# Output.net
KiCad netlist of a schematic drawn in Altium Designer
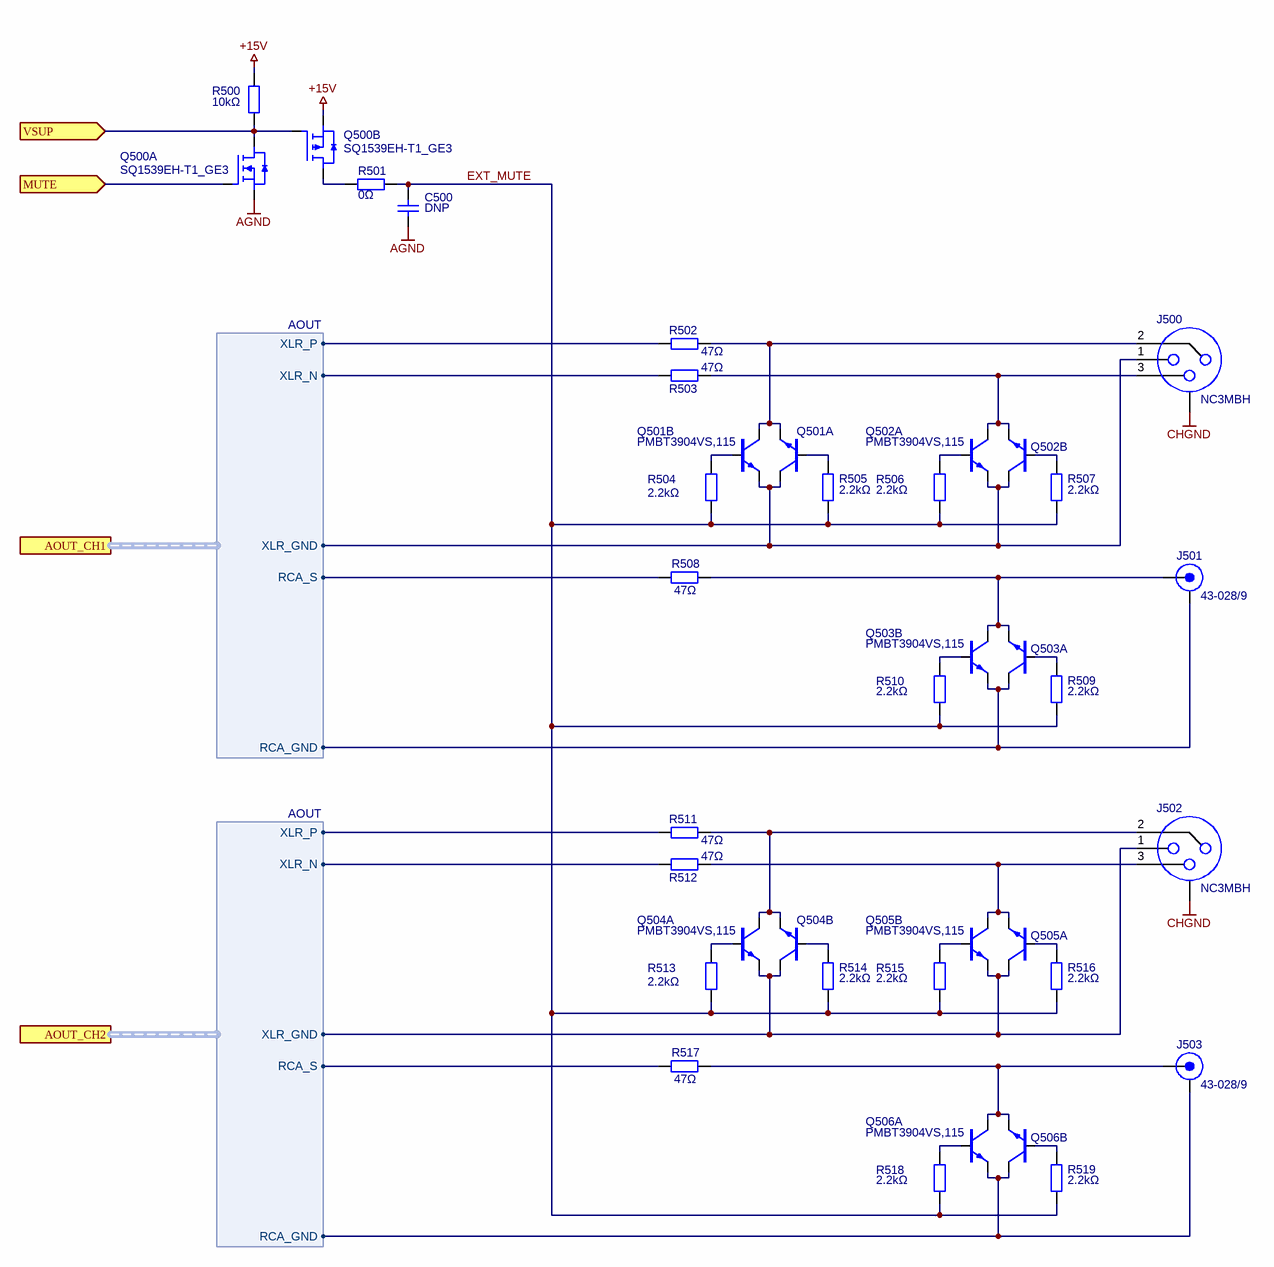
[diagram p0: Output.SchDoc]

(export (version "E")
  (design (tool "Eeschema 10.0.6"))
  (components
    (comp (ref "C500")
      (value "DNP")
      (footprint "SMD0603CAP")
      (description "Ceramic Capacitor")
      (libsource (lib "Audio-Streamer") (part "Capacitor Ceramic"))
    )
    (comp (ref "J500")
      (value "NC3MBH")
      (footprint "NC3MBH")
      (description "XLR Connector Male, Panel Mount")
      (libsource (lib "Audio-Streamer") (part "Connector XLR"))
    )
    (comp (ref "J501")
      (value "43-028/9")
      (footprint "RCA-Plug")
      (description "RCA Connector")
      (libsource (lib "Audio-Streamer") (part "Connector RCA"))
    )
    (comp (ref "J502")
      (value "NC3MBH")
      (footprint "NC3MBH")
      (description "XLR Connector Male, Panel Mount")
      (libsource (lib "Audio-Streamer") (part "Connector XLR"))
    )
    (comp (ref "J503")
      (value "43-028/9")
      (footprint "RCA-Plug")
      (description "RCA Connector")
      (libsource (lib "Audio-Streamer") (part "Connector RCA"))
    )
    (comp (ref "Q500")
      (value "SQ1539EH-T1_GE3")
      (footprint "SOT-363-6")
      (description "Transistor Dual, NMOS & PMOS")
      (libsource (lib "Audio-Streamer") (part "Transistor N/PMOS Dual"))
    )
    (comp (ref "Q501")
      (value "PMBT3904VS,115")
      (footprint "SOT-666")
      (description "Transistor Bipolar Dual")
      (libsource (lib "Audio-Streamer") (part "Transistor Bipolar Dual"))
    )
    (comp (ref "Q502")
      (value "PMBT3904VS,115")
      (footprint "SOT-666")
      (description "Transistor Bipolar Dual")
      (libsource (lib "Audio-Streamer") (part "Transistor Bipolar Dual"))
    )
    (comp (ref "Q503")
      (value "PMBT3904VS,115")
      (footprint "SOT-666")
      (description "Transistor Bipolar Dual")
      (libsource (lib "Audio-Streamer") (part "Transistor Bipolar Dual"))
    )
    (comp (ref "Q504")
      (value "PMBT3904VS,115")
      (footprint "SOT-666")
      (description "Transistor Bipolar Dual")
      (libsource (lib "Audio-Streamer") (part "Transistor Bipolar Dual"))
    )
    (comp (ref "Q505")
      (value "PMBT3904VS,115")
      (footprint "SOT-666")
      (description "Transistor Bipolar Dual")
      (libsource (lib "") (part "Transistor Bipolar Dual_1"))
    )
    (comp (ref "Q506")
      (value "PMBT3904VS,115")
      (footprint "SOT-666")
      (description "Transistor Bipolar Dual")
      (libsource (lib "Audio-Streamer") (part "Transistor Bipolar Dual"))
    )
    (comp (ref "R500")
      (value "10kΩ")
      (footprint "SMD0603RES")
      (description "Resistor")
      (libsource (lib "") (part "Resistor_1"))
    )
    (comp (ref "R501")
      (value "0Ω")
      (footprint "SMD0603RES")
      (description "Resistor")
      (libsource (lib "Audio-Streamer") (part "Resistor"))
    )
    (comp (ref "R502")
      (value "47Ω")
      (footprint "SMD0603RES")
      (description "Resistor Thin Film")
      (fields (field (name "MANUFACTURER PART NO.") "TNPW060347R0BEEA"))
      (libsource (lib "Audio-Streamer") (part "Resistor"))
    )
    (comp (ref "R503")
      (value "47Ω")
      (footprint "SMD0603RES")
      (description "Resistor Thin Film")
      (fields (field (name "MANUFACTURER PART NO.") "TNPW060347R0BEEA"))
      (libsource (lib "Audio-Streamer") (part "Resistor"))
    )
    (comp (ref "R504")
      (value "2.2kΩ")
      (footprint "SMD0603RES")
      (description "Resistor")
      (libsource (lib "") (part "Resistor_1"))
    )
    (comp (ref "R505")
      (value "2.2kΩ")
      (footprint "SMD0603RES")
      (description "Resistor")
      (libsource (lib "") (part "Resistor_2"))
    )
    (comp (ref "R506")
      (value "2.2kΩ")
      (footprint "SMD0603RES")
      (description "Resistor")
      (libsource (lib "") (part "Resistor_1"))
    )
    (comp (ref "R507")
      (value "2.2kΩ")
      (footprint "SMD0603RES")
      (description "Resistor")
      (libsource (lib "") (part "Resistor_2"))
    )
    (comp (ref "R508")
      (value "47Ω")
      (footprint "SMD0603RES")
      (description "Resistor Thin Film")
      (fields (field (name "MANUFACTURER PART NO.") "TNPW060347R0BEEA"))
      (libsource (lib "Audio-Streamer") (part "Resistor"))
    )
    (comp (ref "R509")
      (value "2.2kΩ")
      (footprint "SMD0603RES")
      (description "Resistor")
      (libsource (lib "") (part "Resistor_2"))
    )
    (comp (ref "R510")
      (value "2.2kΩ")
      (footprint "SMD0603RES")
      (description "Resistor")
      (libsource (lib "") (part "Resistor_1"))
    )
    (comp (ref "R511")
      (value "47Ω")
      (footprint "SMD0603RES")
      (description "Resistor Thin Film")
      (fields (field (name "MANUFACTURER PART NO.") "TNPW060347R0BEEA"))
      (libsource (lib "Audio-Streamer") (part "Resistor"))
    )
    (comp (ref "R512")
      (value "47Ω")
      (footprint "SMD0603RES")
      (description "Resistor Thin Film")
      (fields (field (name "MANUFACTURER PART NO.") "TNPW060347R0BEEA"))
      (libsource (lib "Audio-Streamer") (part "Resistor"))
    )
    (comp (ref "R513")
      (value "2.2kΩ")
      (footprint "SMD0603RES")
      (description "Resistor")
      (libsource (lib "") (part "Resistor_1"))
    )
    (comp (ref "R514")
      (value "2.2kΩ")
      (footprint "SMD0603RES")
      (description "Resistor")
      (libsource (lib "") (part "Resistor_2"))
    )
    (comp (ref "R515")
      (value "2.2kΩ")
      (footprint "SMD0603RES")
      (description "Resistor")
      (libsource (lib "") (part "Resistor_1"))
    )
    (comp (ref "R516")
      (value "2.2kΩ")
      (footprint "SMD0603RES")
      (description "Resistor")
      (libsource (lib "") (part "Resistor_2"))
    )
    (comp (ref "R517")
      (value "47Ω")
      (footprint "SMD0603RES")
      (description "Resistor Thin Film")
      (fields (field (name "MANUFACTURER PART NO.") "TNPW060347R0BEEA"))
      (libsource (lib "Audio-Streamer") (part "Resistor"))
    )
    (comp (ref "R518")
      (value "2.2kΩ")
      (footprint "SMD0603RES")
      (description "Resistor")
      (libsource (lib "") (part "Resistor_1"))
    )
    (comp (ref "R519")
      (value "2.2kΩ")
      (footprint "SMD0603RES")
      (description "Resistor")
      (libsource (lib "") (part "Resistor_2"))
    )
  )
  (nets
    (net (code "2") (name "+15V") (class "Default")
      (node (ref "Q500") (pin "4") (pinfunction "S_4") (pintype "passive"))
      (node (ref "R500") (pin "2") (pinfunction "2_2") (pintype "passive"))
    )
    (net (code "3") (name "/EXT_MUTE") (class "Default")
      (node (ref "C500") (pin "1") (pinfunction "1_1") (pintype "passive"))
      (node (ref "R501") (pin "1") (pinfunction "1_1") (pintype "passive"))
      (node (ref "R504") (pin "1") (pinfunction "1_1") (pintype "passive"))
      (node (ref "R505") (pin "1") (pinfunction "1_1") (pintype "passive"))
      (node (ref "R506") (pin "1") (pinfunction "1_1") (pintype "passive"))
      (node (ref "R507") (pin "1") (pinfunction "1_1") (pintype "passive"))
      (node (ref "R509") (pin "1") (pinfunction "1_1") (pintype "passive"))
      (node (ref "R510") (pin "1") (pinfunction "1_1") (pintype "passive"))
      (node (ref "R513") (pin "1") (pinfunction "1_1") (pintype "passive"))
      (node (ref "R514") (pin "1") (pinfunction "1_1") (pintype "passive"))
      (node (ref "R515") (pin "1") (pinfunction "1_1") (pintype "passive"))
      (node (ref "R516") (pin "1") (pinfunction "1_1") (pintype "passive"))
      (node (ref "R518") (pin "1") (pinfunction "1_1") (pintype "passive"))
      (node (ref "R519") (pin "1") (pinfunction "1_1") (pintype "passive"))
    )
    (net (code "4") (name "/MUTE") (class "Default")
      (node (ref "Q500") (pin "2") (pinfunction "G_2") (pintype "passive"))
    )
    (net (code "5") (name "/VSUP") (class "Default")
      (node (ref "Q500") (pin "5") (pinfunction "G_5") (pintype "passive"))
      (node (ref "Q500") (pin "6") (pinfunction "D_6") (pintype "passive"))
      (node (ref "R500") (pin "1") (pinfunction "1_1") (pintype "passive"))
    )
    (net (code "7") (name "AGND") (class "Default")
      (node (ref "C500") (pin "2") (pinfunction "q_2") (pintype "passive"))
      (node (ref "Q500") (pin "1") (pinfunction "S_1") (pintype "passive"))
    )
    (net (code "8") (name "CHGND") (class "Default")
      (node (ref "J500") (pin "0") (pinfunction "0_0") (pintype "passive"))
      (node (ref "J502") (pin "0") (pinfunction "0_0") (pintype "passive"))
    )
    (net (code "9") (name "Net-(J500-Pad1)") (class "Default")
      (node (ref "J500") (pin "1") (pinfunction "1_1") (pintype "passive"))
      (node (ref "Q501") (pin "4") (pinfunction "4_4") (pintype "passive"))
      (node (ref "Q501") (pin "6") (pinfunction "6_6") (pintype "passive"))
      (node (ref "Q502") (pin "1") (pinfunction "1_1") (pintype "passive"))
      (node (ref "Q502") (pin "3") (pinfunction "3_3") (pintype "passive"))
    )
    (net (code "10") (name "Net-(J500-Pad2)") (class "Default")
      (node (ref "J500") (pin "2") (pinfunction "2_2") (pintype "passive"))
      (node (ref "Q501") (pin "1") (pinfunction "1_1") (pintype "passive"))
      (node (ref "Q501") (pin "3") (pinfunction "3_3") (pintype "passive"))
      (node (ref "R502") (pin "1") (pinfunction "1_1") (pintype "passive"))
    )
    (net (code "11") (name "Net-(J500-Pad3)") (class "Default")
      (node (ref "J500") (pin "3") (pinfunction "3_3") (pintype "passive"))
      (node (ref "Q502") (pin "4") (pinfunction "4_4") (pintype "passive"))
      (node (ref "Q502") (pin "6") (pinfunction "6_6") (pintype "passive"))
      (node (ref "R503") (pin "1") (pinfunction "1_1") (pintype "passive"))
    )
    (net (code "12") (name "Net-(J501-Pad1)") (class "Default")
      (node (ref "J501") (pin "1") (pinfunction "1_1") (pintype "passive"))
      (node (ref "Q503") (pin "1") (pinfunction "1_1") (pintype "passive"))
      (node (ref "Q503") (pin "3") (pinfunction "3_3") (pintype "passive"))
      (node (ref "R508") (pin "1") (pinfunction "1_1") (pintype "passive"))
    )
    (net (code "13") (name "Net-(J501-Pad2)") (class "Default")
      (node (ref "J501") (pin "2") (pinfunction "2_2") (pintype "passive"))
      (node (ref "Q503") (pin "4") (pinfunction "4_4") (pintype "passive"))
      (node (ref "Q503") (pin "6") (pinfunction "6_6") (pintype "passive"))
    )
    (net (code "14") (name "Net-(J502-Pad1)") (class "Default")
      (node (ref "J502") (pin "1") (pinfunction "1_1") (pintype "passive"))
      (node (ref "Q504") (pin "1") (pinfunction "1_1") (pintype "passive"))
      (node (ref "Q504") (pin "3") (pinfunction "3_3") (pintype "passive"))
      (node (ref "Q505") (pin "4") (pinfunction "4_4") (pintype "passive"))
      (node (ref "Q505") (pin "6") (pinfunction "6_6") (pintype "passive"))
    )
    (net (code "15") (name "Net-(J502-Pad2)") (class "Default")
      (node (ref "J502") (pin "2") (pinfunction "2_2") (pintype "passive"))
      (node (ref "Q504") (pin "4") (pinfunction "4_4") (pintype "passive"))
      (node (ref "Q504") (pin "6") (pinfunction "6_6") (pintype "passive"))
      (node (ref "R511") (pin "1") (pinfunction "1_1") (pintype "passive"))
    )
    (net (code "16") (name "Net-(J502-Pad3)") (class "Default")
      (node (ref "J502") (pin "3") (pinfunction "3_3") (pintype "passive"))
      (node (ref "Q505") (pin "1") (pinfunction "1_1") (pintype "passive"))
      (node (ref "Q505") (pin "3") (pinfunction "3_3") (pintype "passive"))
      (node (ref "R512") (pin "1") (pinfunction "1_1") (pintype "passive"))
    )
    (net (code "17") (name "Net-(J503-Pad1)") (class "Default")
      (node (ref "J503") (pin "1") (pinfunction "1_1") (pintype "passive"))
      (node (ref "Q506") (pin "4") (pinfunction "4_4") (pintype "passive"))
      (node (ref "Q506") (pin "6") (pinfunction "6_6") (pintype "passive"))
      (node (ref "R517") (pin "1") (pinfunction "1_1") (pintype "passive"))
    )
    (net (code "18") (name "Net-(J503-Pad2)") (class "Default")
      (node (ref "J503") (pin "2") (pinfunction "2_2") (pintype "passive"))
      (node (ref "Q506") (pin "1") (pinfunction "1_1") (pintype "passive"))
      (node (ref "Q506") (pin "3") (pinfunction "3_3") (pintype "passive"))
    )
    (net (code "19") (name "Net-(Q500B-D)") (class "Default")
      (node (ref "Q500") (pin "3") (pinfunction "D_3") (pintype "passive"))
      (node (ref "R501") (pin "2") (pinfunction "2_2") (pintype "passive"))
    )
    (net (code "20") (name "Net-(Q501-Pad2)") (class "Default")
      (node (ref "Q501") (pin "2") (pinfunction "2_2") (pintype "passive"))
      (node (ref "R505") (pin "2") (pinfunction "2_2") (pintype "passive"))
    )
    (net (code "21") (name "Net-(Q501-Pad5)") (class "Default")
      (node (ref "Q501") (pin "5") (pinfunction "5_5") (pintype "passive"))
      (node (ref "R504") (pin "2") (pinfunction "2_2") (pintype "passive"))
    )
    (net (code "22") (name "Net-(Q502-Pad2)") (class "Default")
      (node (ref "Q502") (pin "2") (pinfunction "2_2") (pintype "passive"))
      (node (ref "R506") (pin "2") (pinfunction "2_2") (pintype "passive"))
    )
    (net (code "23") (name "Net-(Q502-Pad5)") (class "Default")
      (node (ref "Q502") (pin "5") (pinfunction "5_5") (pintype "passive"))
      (node (ref "R507") (pin "2") (pinfunction "2_2") (pintype "passive"))
    )
    (net (code "24") (name "Net-(Q503-Pad2)") (class "Default")
      (node (ref "Q503") (pin "2") (pinfunction "2_2") (pintype "passive"))
      (node (ref "R509") (pin "2") (pinfunction "2_2") (pintype "passive"))
    )
    (net (code "25") (name "Net-(Q503-Pad5)") (class "Default")
      (node (ref "Q503") (pin "5") (pinfunction "5_5") (pintype "passive"))
      (node (ref "R510") (pin "2") (pinfunction "2_2") (pintype "passive"))
    )
    (net (code "26") (name "Net-(Q504-Pad2)") (class "Default")
      (node (ref "Q504") (pin "2") (pinfunction "2_2") (pintype "passive"))
      (node (ref "R513") (pin "2") (pinfunction "2_2") (pintype "passive"))
    )
    (net (code "27") (name "Net-(Q504-Pad5)") (class "Default")
      (node (ref "Q504") (pin "5") (pinfunction "5_5") (pintype "passive"))
      (node (ref "R514") (pin "2") (pinfunction "2_2") (pintype "passive"))
    )
    (net (code "28") (name "Net-(Q505-Pad2)") (class "Default")
      (node (ref "Q505") (pin "2") (pinfunction "2_2") (pintype "passive"))
      (node (ref "R516") (pin "2") (pinfunction "2_2") (pintype "passive"))
    )
    (net (code "29") (name "Net-(Q505-Pad5)") (class "Default")
      (node (ref "Q505") (pin "5") (pinfunction "5_5") (pintype "passive"))
      (node (ref "R515") (pin "2") (pinfunction "2_2") (pintype "passive"))
    )
    (net (code "30") (name "Net-(Q506-Pad2)") (class "Default")
      (node (ref "Q506") (pin "2") (pinfunction "2_2") (pintype "passive"))
      (node (ref "R518") (pin "2") (pinfunction "2_2") (pintype "passive"))
    )
    (net (code "31") (name "Net-(Q506-Pad5)") (class "Default")
      (node (ref "Q506") (pin "5") (pinfunction "5_5") (pintype "passive"))
      (node (ref "R519") (pin "2") (pinfunction "2_2") (pintype "passive"))
    )
    (net (code "32") (name "unconnected-(R502-Pad2)") (class "Default")
      (node (ref "R502") (pin "2") (pinfunction "2_2") (pintype "passive"))
    )
    (net (code "33") (name "unconnected-(R503-Pad2)") (class "Default")
      (node (ref "R503") (pin "2") (pinfunction "2_2") (pintype "passive"))
    )
    (net (code "34") (name "unconnected-(R508-Pad2)") (class "Default")
      (node (ref "R508") (pin "2") (pinfunction "2_2") (pintype "passive"))
    )
    (net (code "35") (name "unconnected-(R511-Pad2)") (class "Default")
      (node (ref "R511") (pin "2") (pinfunction "2_2") (pintype "passive"))
    )
    (net (code "36") (name "unconnected-(R512-Pad2)") (class "Default")
      (node (ref "R512") (pin "2") (pinfunction "2_2") (pintype "passive"))
    )
    (net (code "37") (name "unconnected-(R517-Pad2)") (class "Default")
      (node (ref "R517") (pin "2") (pinfunction "2_2") (pintype "passive"))
    )
  )
)
